# New_Buggy_2015.net
KiCad netlist of a schematic drawn in EAGLE
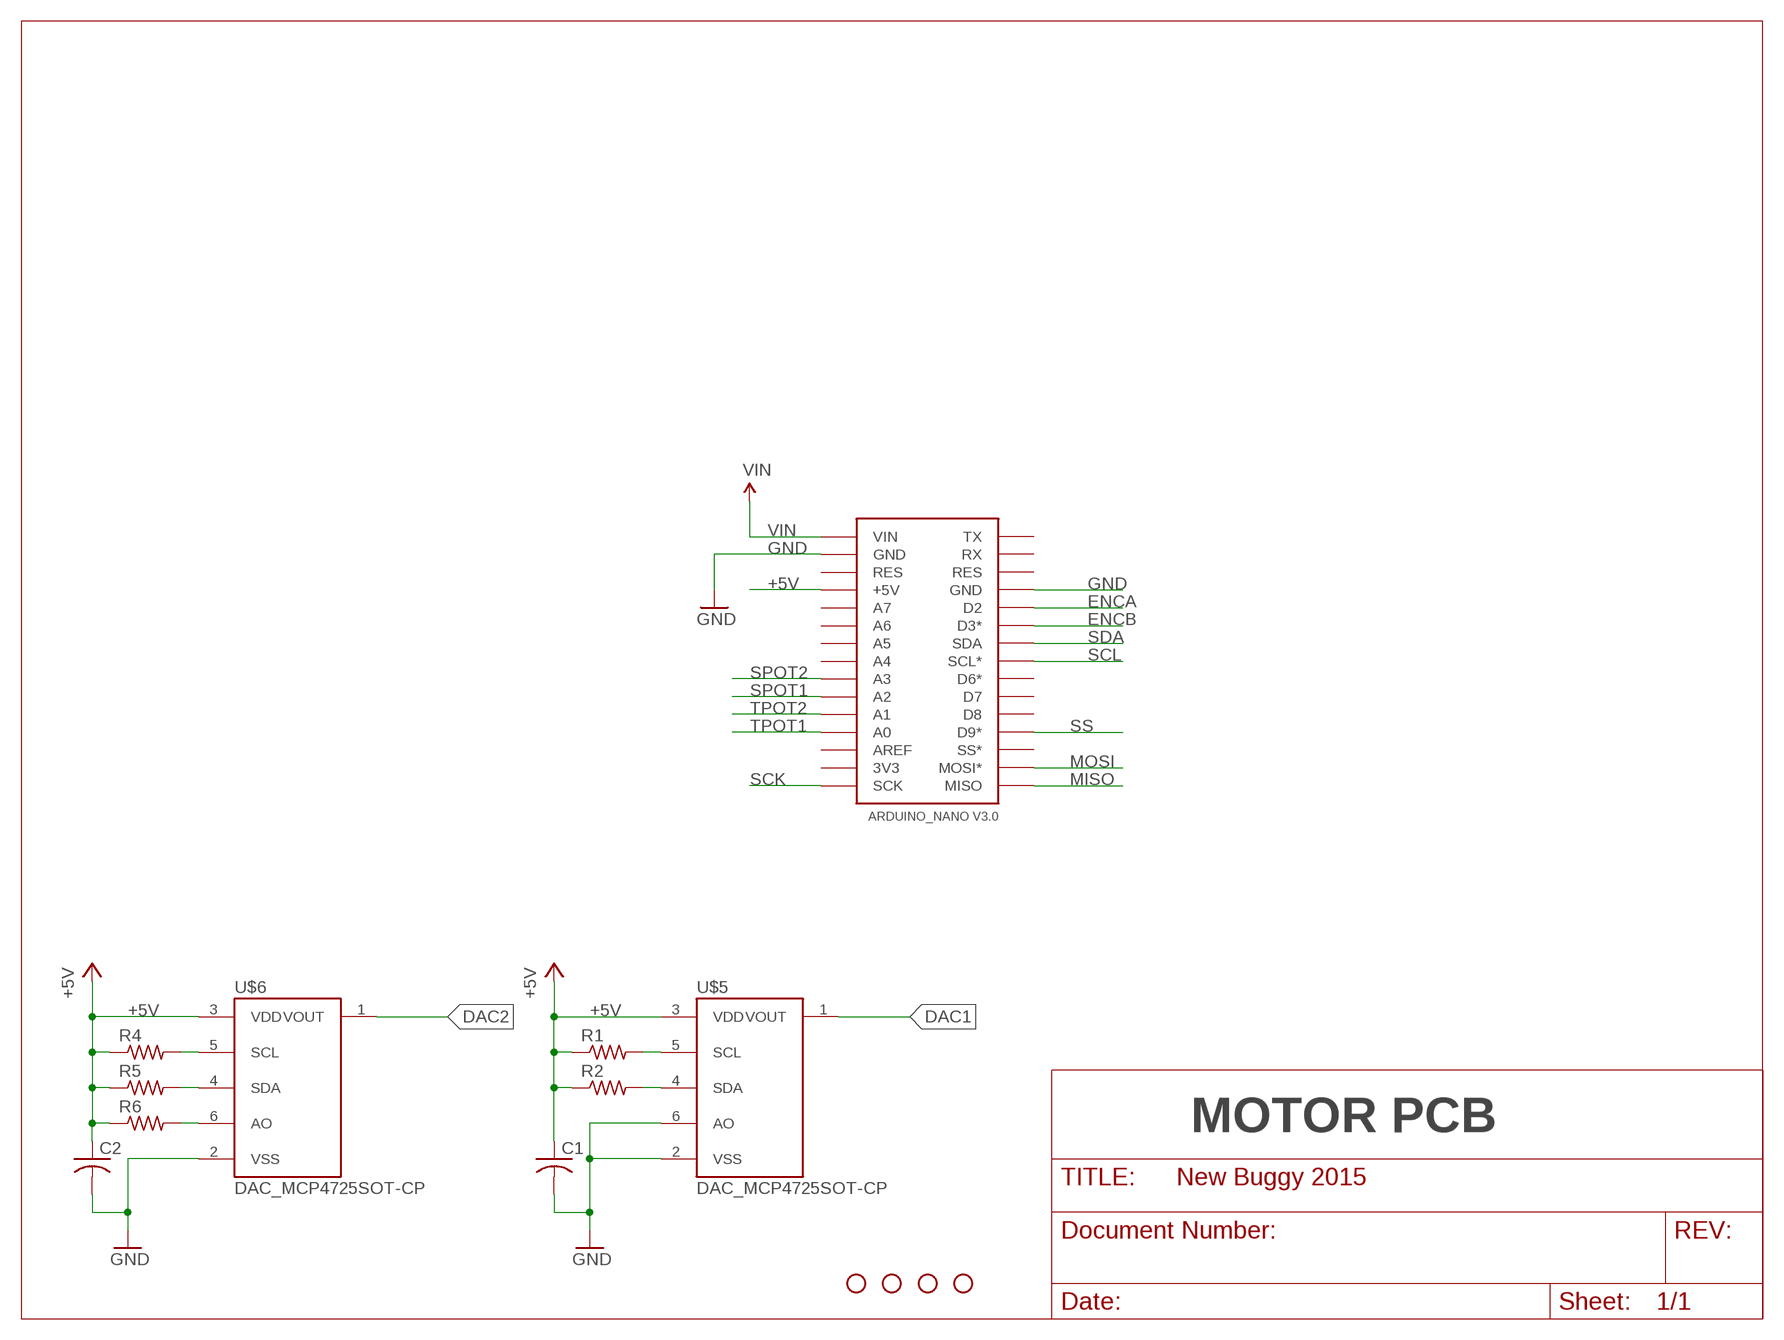
[diagram p0: schematic, sheet 1]

(export (version "E")
  (design (tool "Eeschema 10.0.6"))
  (components
    (comp (ref "C1")
      (value "C-USC1206")
      (footprint "eagle-import:C1206")
      (libsource (lib "eagle-import") (part "C-USC1206"))
    )
    (comp (ref "C2")
      (value "C-USC1206")
      (footprint "eagle-import:C1206")
      (libsource (lib "eagle-import") (part "C-USC1206"))
    )
    (comp (ref "R1")
      (value "R-US_R1206")
      (footprint "eagle-import:R1206")
      (libsource (lib "eagle-import") (part "R-US_R1206"))
    )
    (comp (ref "R2")
      (value "R-US_R1206")
      (footprint "eagle-import:R1206")
      (libsource (lib "eagle-import") (part "R-US_R1206"))
    )
    (comp (ref "R4")
      (value "R-US_R1206")
      (footprint "eagle-import:R1206")
      (libsource (lib "eagle-import") (part "R-US_R1206"))
    )
    (comp (ref "R5")
      (value "R-US_R1206")
      (footprint "eagle-import:R1206")
      (libsource (lib "eagle-import") (part "R-US_R1206"))
    )
    (comp (ref "R6")
      (value "R-US_R1206")
      (footprint "eagle-import:R1206")
      (libsource (lib "eagle-import") (part "R-US_R1206"))
    )
    (comp (ref "STANDOFF1")
      (value "STAND-OFF")
      (footprint "eagle-import:STAND-OFF")
      (libsource (lib "eagle-import") (part "STAND-OFF"))
    )
    (comp (ref "STANDOFF2")
      (value "STAND-OFF")
      (footprint "eagle-import:STAND-OFF")
      (libsource (lib "eagle-import") (part "STAND-OFF"))
    )
    (comp (ref "STANDOFF3")
      (value "STAND-OFF")
      (footprint "eagle-import:STAND-OFF")
      (libsource (lib "eagle-import") (part "STAND-OFF"))
    )
    (comp (ref "STANDOFF4")
      (value "STAND-OFF")
      (footprint "eagle-import:STAND-OFF")
      (libsource (lib "eagle-import") (part "STAND-OFF"))
    )
    (comp (ref "U$3")
      (value "ARDUINO_NANO")
      (footprint "eagle-import:ARDUINO_NANO")
      (libsource (lib "eagle-import") (part "ARDUINO_NANO"))
    )
    (comp (ref "U$5")
      (value "DAC_MCP4725SOT-CP")
      (footprint "eagle-import:SOT23-6-MCP4725")
      (libsource (lib "eagle-import") (part "DAC_MCP4725SOT-CP"))
    )
    (comp (ref "U$6")
      (value "DAC_MCP4725SOT-CP")
      (footprint "eagle-import:SOT23-6-MCP4725")
      (libsource (lib "eagle-import") (part "DAC_MCP4725SOT-CP"))
    )
  )
  (nets
    (net (code "1") (name "+5V") (class "Default")
      (node (ref "C1") (pin "1") (pinfunction "1_1") (pintype "passive"))
      (node (ref "C2") (pin "1") (pinfunction "1_1") (pintype "passive"))
      (node (ref "R1") (pin "1") (pinfunction "1_1") (pintype "passive"))
      (node (ref "R2") (pin "1") (pinfunction "1_1") (pintype "passive"))
      (node (ref "R4") (pin "1") (pinfunction "1_1") (pintype "passive"))
      (node (ref "R5") (pin "1") (pinfunction "1_1") (pintype "passive"))
      (node (ref "R6") (pin "1") (pinfunction "1_1") (pintype "passive"))
      (node (ref "U$3") (pin "+5V") (pinfunction "+5V_+5V") (pintype "bidirectional"))
      (node (ref "U$5") (pin "3") (pinfunction "VDD_3") (pintype "bidirectional"))
      (node (ref "U$6") (pin "3") (pinfunction "VDD_3") (pintype "bidirectional"))
    )
    (net (code "2") (name "/ENCA") (class "Default")
      (node (ref "U$3") (pin "D2") (pinfunction "D2_D2") (pintype "bidirectional"))
    )
    (net (code "3") (name "/ENCB") (class "Default")
      (node (ref "U$3") (pin "D3*") (pinfunction "D3*_D3*") (pintype "bidirectional"))
    )
    (net (code "4") (name "/MISO") (class "Default")
      (node (ref "U$3") (pin "MISO") (pinfunction "MISO_MISO") (pintype "bidirectional"))
    )
    (net (code "5") (name "/MOSI") (class "Default")
      (node (ref "U$3") (pin "MOSI*") (pinfunction "MOSI*_MOSI*") (pintype "bidirectional"))
    )
    (net (code "6") (name "/SCK") (class "Default")
      (node (ref "U$3") (pin "SCK") (pinfunction "SCK_SCK") (pintype "bidirectional"))
    )
    (net (code "7") (name "/SCL") (class "Default")
      (node (ref "R1") (pin "2") (pinfunction "2_2") (pintype "passive"))
      (node (ref "R4") (pin "2") (pinfunction "2_2") (pintype "passive"))
      (node (ref "U$3") (pin "SCL*") (pinfunction "SCL*_SCL*") (pintype "bidirectional"))
      (node (ref "U$5") (pin "5") (pinfunction "SCL_5") (pintype "bidirectional"))
      (node (ref "U$6") (pin "5") (pinfunction "SCL_5") (pintype "bidirectional"))
    )
    (net (code "8") (name "/SDA") (class "Default")
      (node (ref "R2") (pin "2") (pinfunction "2_2") (pintype "passive"))
      (node (ref "R5") (pin "2") (pinfunction "2_2") (pintype "passive"))
      (node (ref "U$3") (pin "SDA") (pinfunction "SDA_SDA") (pintype "bidirectional"))
      (node (ref "U$5") (pin "4") (pinfunction "SDA_4") (pintype "bidirectional"))
      (node (ref "U$6") (pin "4") (pinfunction "SDA_4") (pintype "bidirectional"))
    )
    (net (code "9") (name "/SPOT1") (class "Default")
      (node (ref "U$3") (pin "A2") (pinfunction "A2_A2") (pintype "bidirectional"))
    )
    (net (code "10") (name "/SPOT2") (class "Default")
      (node (ref "U$3") (pin "A3") (pinfunction "A3_A3") (pintype "bidirectional"))
    )
    (net (code "11") (name "/SS") (class "Default")
      (node (ref "U$3") (pin "D9*") (pinfunction "D9*_D9*") (pintype "bidirectional"))
    )
    (net (code "12") (name "/TPOT1") (class "Default")
      (node (ref "U$3") (pin "A0") (pinfunction "A0_A0") (pintype "bidirectional"))
    )
    (net (code "13") (name "/TPOT2") (class "Default")
      (node (ref "U$3") (pin "A1") (pinfunction "A1_A1") (pintype "bidirectional"))
    )
    (net (code "14") (name "DAC1") (class "Default")
      (node (ref "U$5") (pin "1") (pinfunction "VOUT_1") (pintype "bidirectional"))
    )
    (net (code "15") (name "DAC2") (class "Default")
      (node (ref "U$6") (pin "1") (pinfunction "VOUT_1") (pintype "bidirectional"))
    )
    (net (code "16") (name "GND") (class "Default")
      (node (ref "C1") (pin "2") (pinfunction "2_2") (pintype "passive"))
      (node (ref "C2") (pin "2") (pinfunction "2_2") (pintype "passive"))
      (node (ref "U$3") (pin "GND") (pinfunction "GND_GND") (pintype "bidirectional"))
      (node (ref "U$3") (pin "GND@1") (pinfunction "GND_GND@1") (pintype "bidirectional"))
      (node (ref "U$5") (pin "2") (pinfunction "VSS_2") (pintype "bidirectional"))
      (node (ref "U$5") (pin "6") (pinfunction "AO_6") (pintype "bidirectional"))
      (node (ref "U$6") (pin "2") (pinfunction "VSS_2") (pintype "bidirectional"))
    )
    (net (code "17") (name "Net-(U$6-AO)") (class "Default")
      (node (ref "R6") (pin "2") (pinfunction "2_2") (pintype "passive"))
      (node (ref "U$6") (pin "6") (pinfunction "AO_6") (pintype "bidirectional"))
    )
    (net (code "18") (name "VIN") (class "Default")
      (node (ref "U$3") (pin "VIN") (pinfunction "VIN_VIN") (pintype "bidirectional"))
    )
    (net (code "19") (name "unconnected-(U$3-Pad3V3)") (class "Default")
      (node (ref "U$3") (pin "3V3") (pinfunction "3V3_3V3") (pintype "bidirectional"))
    )
    (net (code "20") (name "unconnected-(U$3-PadA4)") (class "Default")
      (node (ref "U$3") (pin "A4") (pinfunction "A4_A4") (pintype "bidirectional"))
    )
    (net (code "21") (name "unconnected-(U$3-PadA5)") (class "Default")
      (node (ref "U$3") (pin "A5") (pinfunction "A5_A5") (pintype "bidirectional"))
    )
    (net (code "22") (name "unconnected-(U$3-PadA6)") (class "Default")
      (node (ref "U$3") (pin "A6") (pinfunction "A6_A6") (pintype "bidirectional"))
    )
    (net (code "23") (name "unconnected-(U$3-PadA7)") (class "Default")
      (node (ref "U$3") (pin "A7") (pinfunction "A7_A7") (pintype "bidirectional"))
    )
    (net (code "24") (name "unconnected-(U$3-PadAREF)") (class "Default")
      (node (ref "U$3") (pin "AREF") (pinfunction "AREF_AREF") (pintype "bidirectional"))
    )
    (net (code "25") (name "unconnected-(U$3-PadD6*)") (class "Default")
      (node (ref "U$3") (pin "D6*") (pinfunction "D6*_D6*") (pintype "bidirectional"))
    )
    (net (code "26") (name "unconnected-(U$3-PadD7)") (class "Default")
      (node (ref "U$3") (pin "D7") (pinfunction "D7_D7") (pintype "bidirectional"))
    )
    (net (code "27") (name "unconnected-(U$3-PadD8)") (class "Default")
      (node (ref "U$3") (pin "D8") (pinfunction "D8_D8") (pintype "bidirectional"))
    )
    (net (code "28") (name "unconnected-(U$3-PadRES)") (class "Default")
      (node (ref "U$3") (pin "RES") (pinfunction "RES_RES") (pintype "bidirectional"))
    )
    (net (code "29") (name "unconnected-(U$3-PadRX)") (class "Default")
      (node (ref "U$3") (pin "RX") (pinfunction "RX_RX") (pintype "bidirectional"))
    )
    (net (code "30") (name "unconnected-(U$3-PadSS*)") (class "Default")
      (node (ref "U$3") (pin "SS*") (pinfunction "SS*_SS*") (pintype "bidirectional"))
    )
    (net (code "31") (name "unconnected-(U$3-PadTX)") (class "Default")
      (node (ref "U$3") (pin "TX") (pinfunction "TX_TX") (pintype "bidirectional"))
    )
    (net (code "32") (name "unconnected-(U$3-RES-PadRES@1)") (class "Default")
      (node (ref "U$3") (pin "RES@1") (pinfunction "RES_RES@1") (pintype "bidirectional"))
    )
  )
)
